# LNA_v3.net
KiCad netlist of a schematic drawn in EAGLE
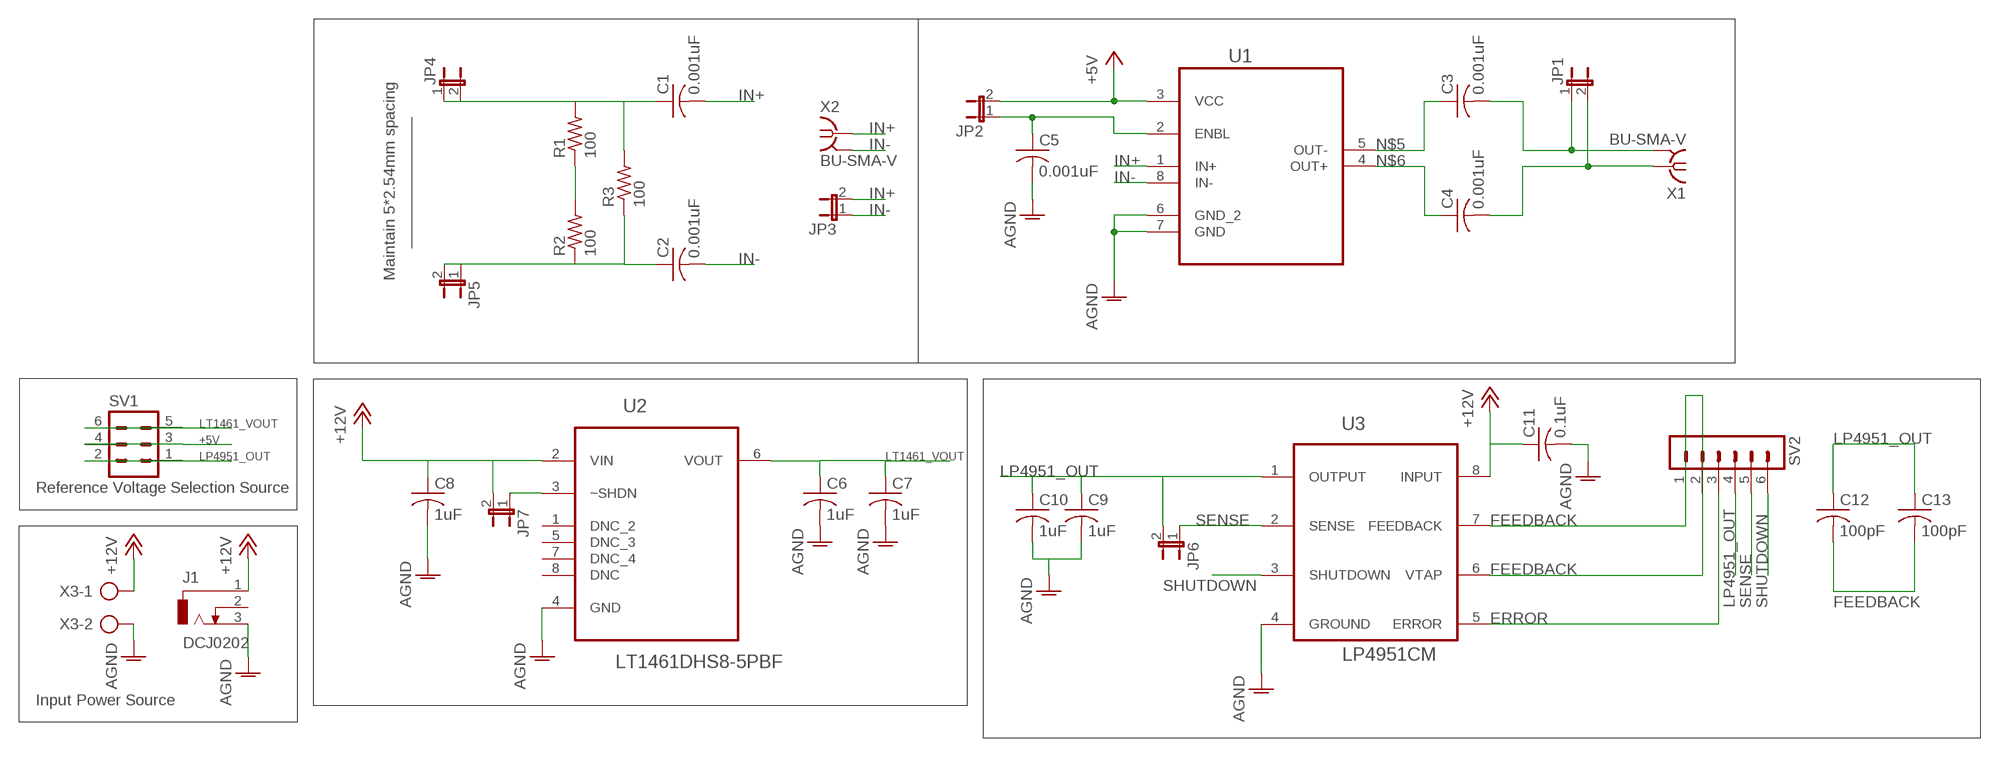
[diagram p0: schematic, sheet 1]

(export (version "E")
  (design (tool "Eeschema 10.0.6"))
  (components
    (comp (ref "C1")
      (value "0.001uF")
      (footprint "eagle-import:C0805")
      (libsource (lib "eagle-import") (part "C-USC0805"))
    )
    (comp (ref "C2")
      (value "0.001uF")
      (footprint "eagle-import:C0805")
      (libsource (lib "eagle-import") (part "C-USC0805"))
    )
    (comp (ref "C3")
      (value "0.001uF")
      (footprint "eagle-import:C0805")
      (libsource (lib "eagle-import") (part "C-USC0805"))
    )
    (comp (ref "C4")
      (value "0.001uF")
      (footprint "eagle-import:C0805")
      (libsource (lib "eagle-import") (part "C-USC0805"))
    )
    (comp (ref "C5")
      (value "0.001uF")
      (footprint "eagle-import:C0805")
      (libsource (lib "eagle-import") (part "C-USC0805"))
    )
    (comp (ref "C6")
      (value "1uF")
      (footprint "eagle-import:C0805")
      (libsource (lib "eagle-import") (part "C-USC0805"))
    )
    (comp (ref "C7")
      (value "1uF")
      (footprint "eagle-import:C0805")
      (libsource (lib "eagle-import") (part "C-USC0805"))
    )
    (comp (ref "C8")
      (value "1uF")
      (footprint "eagle-import:C0805")
      (libsource (lib "eagle-import") (part "C-USC0805"))
    )
    (comp (ref "C9")
      (value "1uF")
      (footprint "eagle-import:C0805")
      (libsource (lib "eagle-import") (part "C-USC0805"))
    )
    (comp (ref "C10")
      (value "1uF")
      (footprint "eagle-import:C0805")
      (libsource (lib "eagle-import") (part "C-USC0805"))
    )
    (comp (ref "C11")
      (value "0.1uF")
      (footprint "eagle-import:C0805")
      (libsource (lib "eagle-import") (part "C-USC0805"))
    )
    (comp (ref "C12")
      (value "100pF")
      (footprint "eagle-import:C0805")
      (libsource (lib "eagle-import") (part "C-USC0805"))
    )
    (comp (ref "C13")
      (value "100pF")
      (footprint "eagle-import:C0805")
      (libsource (lib "eagle-import") (part "C-USC0805"))
    )
    (comp (ref "J1")
      (value "DCJ0202")
      (footprint "eagle-import:DCJ0202")
      (libsource (lib "eagle-import") (part "DCJ0202"))
    )
    (comp (ref "JP1")
      (value "JP1E")
      (footprint "eagle-import:JP1")
      (libsource (lib "eagle-import") (part "JP1E"))
    )
    (comp (ref "JP2")
      (value "JP1E")
      (footprint "eagle-import:JP1")
      (libsource (lib "eagle-import") (part "JP1E"))
    )
    (comp (ref "JP3")
      (value "JP1E")
      (footprint "eagle-import:JP1")
      (libsource (lib "eagle-import") (part "JP1E"))
    )
    (comp (ref "JP4")
      (value "JP1E")
      (footprint "eagle-import:JP1")
      (libsource (lib "eagle-import") (part "JP1E"))
    )
    (comp (ref "JP5")
      (value "JP1E")
      (footprint "eagle-import:JP1")
      (libsource (lib "eagle-import") (part "JP1E"))
    )
    (comp (ref "JP6")
      (value "JP1E")
      (footprint "eagle-import:JP1")
      (libsource (lib "eagle-import") (part "JP1E"))
    )
    (comp (ref "JP7")
      (value "JP1E")
      (footprint "eagle-import:JP1")
      (libsource (lib "eagle-import") (part "JP1E"))
    )
    (comp (ref "R1")
      (value "100")
      (footprint "eagle-import:R0805")
      (libsource (lib "eagle-import") (part "R-US_R0805"))
    )
    (comp (ref "R2")
      (value "100")
      (footprint "eagle-import:R0805")
      (libsource (lib "eagle-import") (part "R-US_R0805"))
    )
    (comp (ref "R3")
      (value "100")
      (footprint "eagle-import:R0805")
      (libsource (lib "eagle-import") (part "R-US_R0805"))
    )
    (comp (ref "SV1")
      (value "MA03-2")
      (footprint "eagle-import:MA03-2")
      (libsource (lib "eagle-import") (part "MA03-2"))
    )
    (comp (ref "SV2")
      (value "MA06-1")
      (footprint "eagle-import:MA06-1")
      (libsource (lib "eagle-import") (part "MA06-1"))
    )
    (comp (ref "U1")
      (value "AD8350ARMZ20")
      (footprint "eagle-import:SOP65P490X110-8N")
      (libsource (lib "eagle-import") (part "AD8350ARMZ20"))
    )
    (comp (ref "U2")
      (value "LT1461DHS8-5PBF")
      (footprint "eagle-import:SOIC127P600X175-8N")
      (fields (field (name "MPN") "LT1461DHS8-5#PBF"))
      (libsource (lib "eagle-import") (part "LT1461DHS8-5PBF"))
    )
    (comp (ref "U3")
      (value "LP4951CM")
      (footprint "eagle-import:SOIC127P600X175-8N")
      (libsource (lib "eagle-import") (part "LP4951CM"))
    )
    (comp (ref "X1")
      (value "BU-SMA-V")
      (footprint "eagle-import:BU-SMA-V")
      (libsource (lib "eagle-import") (part "BU-SMA-V"))
    )
    (comp (ref "X2")
      (value "BU-SMA-V")
      (footprint "eagle-import:BU-SMA-V")
      (libsource (lib "eagle-import") (part "BU-SMA-V"))
    )
    (comp (ref "X3")
      (value "AK500/2")
      (footprint "eagle-import:AK500_2")
      (libsource (lib "eagle-import") (part "AK500/2"))
    )
  )
  (nets
    (net (code "1") (name "+5V") (class "Default")
      (node (ref "JP2") (pin "2") (pinfunction "2_2") (pintype "passive"))
      (node (ref "SV1") (pin "3") (pinfunction "3_3") (pintype "passive"))
      (node (ref "SV1") (pin "4") (pinfunction "4_4") (pintype "passive"))
      (node (ref "U1") (pin "3") (pinfunction "VCC_3") (pintype "power_in"))
    )
    (net (code "2") (name "+12V") (class "Default")
      (node (ref "C11") (pin "1") (pinfunction "1_1") (pintype "passive"))
      (node (ref "C8") (pin "1") (pinfunction "1_1") (pintype "passive"))
      (node (ref "J1") (pin "1") (pinfunction "1_1") (pintype "passive"))
      (node (ref "JP7") (pin "2") (pinfunction "2_2") (pintype "passive"))
      (node (ref "U2") (pin "2") (pinfunction "VIN_2") (pintype "power_in"))
      (node (ref "U3") (pin "8") (pinfunction "INPUT_8") (pintype "bidirectional"))
      (node (ref "X3") (pin "1") (pinfunction "KL_1") (pintype "passive"))
    )
    (net (code "3") (name "/ERROR") (class "Default")
      (node (ref "SV2") (pin "3") (pinfunction "3_3") (pintype "passive"))
      (node (ref "U3") (pin "5") (pinfunction "ERROR_5") (pintype "bidirectional"))
    )
    (net (code "4") (name "/FEEDBACK") (class "Default")
      (node (ref "C12") (pin "2") (pinfunction "2_2") (pintype "passive"))
      (node (ref "C13") (pin "2") (pinfunction "2_2") (pintype "passive"))
      (node (ref "SV2") (pin "1") (pinfunction "1_1") (pintype "passive"))
      (node (ref "SV2") (pin "2") (pinfunction "2_2") (pintype "passive"))
      (node (ref "U3") (pin "6") (pinfunction "VTAP_6") (pintype "bidirectional"))
      (node (ref "U3") (pin "7") (pinfunction "FEEDBACK_7") (pintype "bidirectional"))
    )
    (net (code "5") (name "/IN+") (class "Default")
      (node (ref "C1") (pin "2") (pinfunction "2_2") (pintype "passive"))
      (node (ref "JP3") (pin "2") (pinfunction "2_2") (pintype "passive"))
      (node (ref "U1") (pin "1") (pinfunction "IN+_1") (pintype "passive"))
      (node (ref "X2") (pin "1") (pinfunction "1_1") (pintype "passive"))
    )
    (net (code "6") (name "/IN-") (class "Default")
      (node (ref "C2") (pin "2") (pinfunction "2_2") (pintype "passive"))
      (node (ref "JP3") (pin "1") (pinfunction "1_1") (pintype "passive"))
      (node (ref "U1") (pin "8") (pinfunction "IN-_8") (pintype "passive"))
      (node (ref "X2") (pin "2") (pinfunction "2_2") (pintype "passive"))
      (node (ref "X2") (pin "3") (pinfunction "2_3") (pintype "passive"))
      (node (ref "X2") (pin "4") (pinfunction "2_4") (pintype "passive"))
      (node (ref "X2") (pin "5") (pinfunction "2_5") (pintype "passive"))
    )
    (net (code "7") (name "/LP4951_OUT") (class "Default")
      (node (ref "C10") (pin "1") (pinfunction "1_1") (pintype "passive"))
      (node (ref "C12") (pin "1") (pinfunction "1_1") (pintype "passive"))
      (node (ref "C13") (pin "1") (pinfunction "1_1") (pintype "passive"))
      (node (ref "C9") (pin "1") (pinfunction "1_1") (pintype "passive"))
      (node (ref "JP6") (pin "2") (pinfunction "2_2") (pintype "passive"))
      (node (ref "SV1") (pin "1") (pinfunction "1_1") (pintype "passive"))
      (node (ref "SV1") (pin "2") (pinfunction "2_2") (pintype "passive"))
      (node (ref "SV2") (pin "4") (pinfunction "4_4") (pintype "passive"))
      (node (ref "U3") (pin "1") (pinfunction "OUTPUT_1") (pintype "bidirectional"))
    )
    (net (code "8") (name "/LT1461_VOUT") (class "Default")
      (node (ref "C6") (pin "1") (pinfunction "1_1") (pintype "passive"))
      (node (ref "C7") (pin "1") (pinfunction "1_1") (pintype "passive"))
      (node (ref "SV1") (pin "5") (pinfunction "5_5") (pintype "passive"))
      (node (ref "SV1") (pin "6") (pinfunction "6_6") (pintype "passive"))
      (node (ref "U2") (pin "6") (pinfunction "VOUT_6") (pintype "output"))
    )
    (net (code "9") (name "/N$5") (class "Default")
      (node (ref "C3") (pin "1") (pinfunction "1_1") (pintype "passive"))
      (node (ref "U1") (pin "5") (pinfunction "OUT-_5") (pintype "passive"))
    )
    (net (code "10") (name "/N$6") (class "Default")
      (node (ref "C4") (pin "1") (pinfunction "1_1") (pintype "passive"))
      (node (ref "U1") (pin "4") (pinfunction "OUT+_4") (pintype "passive"))
    )
    (net (code "11") (name "/SENSE") (class "Default")
      (node (ref "JP6") (pin "1") (pinfunction "1_1") (pintype "passive"))
      (node (ref "SV2") (pin "5") (pinfunction "5_5") (pintype "passive"))
      (node (ref "U3") (pin "2") (pinfunction "SENSE_2") (pintype "bidirectional"))
    )
    (net (code "12") (name "/SHUTDOWN") (class "Default")
      (node (ref "SV2") (pin "6") (pinfunction "6_6") (pintype "passive"))
      (node (ref "U3") (pin "3") (pinfunction "SHUTDOWN_3") (pintype "bidirectional"))
    )
    (net (code "13") (name "AGND") (class "Default")
      (node (ref "C10") (pin "2") (pinfunction "2_2") (pintype "passive"))
      (node (ref "C11") (pin "2") (pinfunction "2_2") (pintype "passive"))
      (node (ref "C5") (pin "2") (pinfunction "2_2") (pintype "passive"))
      (node (ref "C6") (pin "2") (pinfunction "2_2") (pintype "passive"))
      (node (ref "C7") (pin "2") (pinfunction "2_2") (pintype "passive"))
      (node (ref "C8") (pin "2") (pinfunction "2_2") (pintype "passive"))
      (node (ref "C9") (pin "2") (pinfunction "2_2") (pintype "passive"))
      (node (ref "J1") (pin "3") (pinfunction "3_3") (pintype "passive"))
      (node (ref "U1") (pin "6") (pinfunction "GND_2_6") (pintype "passive"))
      (node (ref "U1") (pin "7") (pinfunction "GND_7") (pintype "passive"))
      (node (ref "U2") (pin "4") (pinfunction "GND_4") (pintype "passive"))
      (node (ref "U3") (pin "4") (pinfunction "GROUND_4") (pintype "bidirectional"))
      (node (ref "X3") (pin "2") (pinfunction "KL_2") (pintype "passive"))
    )
    (net (code "14") (name "Net-(C1-Pad1)") (class "Default")
      (node (ref "C1") (pin "1") (pinfunction "1_1") (pintype "passive"))
      (node (ref "JP4") (pin "1") (pinfunction "1_1") (pintype "passive"))
      (node (ref "JP4") (pin "2") (pinfunction "2_2") (pintype "passive"))
      (node (ref "R1") (pin "2") (pinfunction "2_2") (pintype "passive"))
      (node (ref "R3") (pin "2") (pinfunction "2_2") (pintype "passive"))
    )
    (net (code "15") (name "Net-(C2-Pad1)") (class "Default")
      (node (ref "C2") (pin "1") (pinfunction "1_1") (pintype "passive"))
      (node (ref "JP5") (pin "1") (pinfunction "1_1") (pintype "passive"))
      (node (ref "JP5") (pin "2") (pinfunction "2_2") (pintype "passive"))
      (node (ref "R2") (pin "1") (pinfunction "1_1") (pintype "passive"))
      (node (ref "R3") (pin "1") (pinfunction "1_1") (pintype "passive"))
    )
    (net (code "16") (name "Net-(C3-Pad2)") (class "Default")
      (node (ref "C3") (pin "2") (pinfunction "2_2") (pintype "passive"))
      (node (ref "JP1") (pin "1") (pinfunction "1_1") (pintype "passive"))
      (node (ref "X1") (pin "2") (pinfunction "2_2") (pintype "passive"))
      (node (ref "X1") (pin "3") (pinfunction "2_3") (pintype "passive"))
      (node (ref "X1") (pin "4") (pinfunction "2_4") (pintype "passive"))
      (node (ref "X1") (pin "5") (pinfunction "2_5") (pintype "passive"))
    )
    (net (code "17") (name "Net-(C4-Pad2)") (class "Default")
      (node (ref "C4") (pin "2") (pinfunction "2_2") (pintype "passive"))
      (node (ref "JP1") (pin "2") (pinfunction "2_2") (pintype "passive"))
      (node (ref "X1") (pin "1") (pinfunction "1_1") (pintype "passive"))
    )
    (net (code "18") (name "Net-(R1-Pad1)") (class "Default")
      (node (ref "R1") (pin "1") (pinfunction "1_1") (pintype "passive"))
      (node (ref "R2") (pin "2") (pinfunction "2_2") (pintype "passive"))
    )
    (net (code "19") (name "Net-(U1-ENBL)") (class "Default")
      (node (ref "C5") (pin "1") (pinfunction "1_1") (pintype "passive"))
      (node (ref "JP2") (pin "1") (pinfunction "1_1") (pintype "passive"))
      (node (ref "U1") (pin "2") (pinfunction "ENBL_2") (pintype "power_in"))
    )
    (net (code "20") (name "Net-(U2-~{SHDN})") (class "Default")
      (node (ref "JP7") (pin "1") (pinfunction "1_1") (pintype "passive"))
      (node (ref "U2") (pin "3") (pinfunction "~{SHDN}_3") (pintype "input"))
    )
    (net (code "21") (name "unconnected-(J1-Pad2)") (class "Default")
      (node (ref "J1") (pin "2") (pinfunction "2_2") (pintype "passive"))
    )
    (net (code "22") (name "unconnected-(U2-DNC-Pad8)") (class "Default")
      (node (ref "U2") (pin "8") (pinfunction "DNC_8") (pintype "no_connect"))
    )
    (net (code "23") (name "unconnected-(U2-DNC_2-Pad1)") (class "Default")
      (node (ref "U2") (pin "1") (pinfunction "DNC_2_1") (pintype "no_connect"))
    )
    (net (code "24") (name "unconnected-(U2-DNC_3-Pad5)") (class "Default")
      (node (ref "U2") (pin "5") (pinfunction "DNC_3_5") (pintype "no_connect"))
    )
    (net (code "25") (name "unconnected-(U2-DNC_4-Pad7)") (class "Default")
      (node (ref "U2") (pin "7") (pinfunction "DNC_4_7") (pintype "no_connect"))
    )
  )
)
